# main.net
KiCad netlist of a schematic drawn in Altium Designer
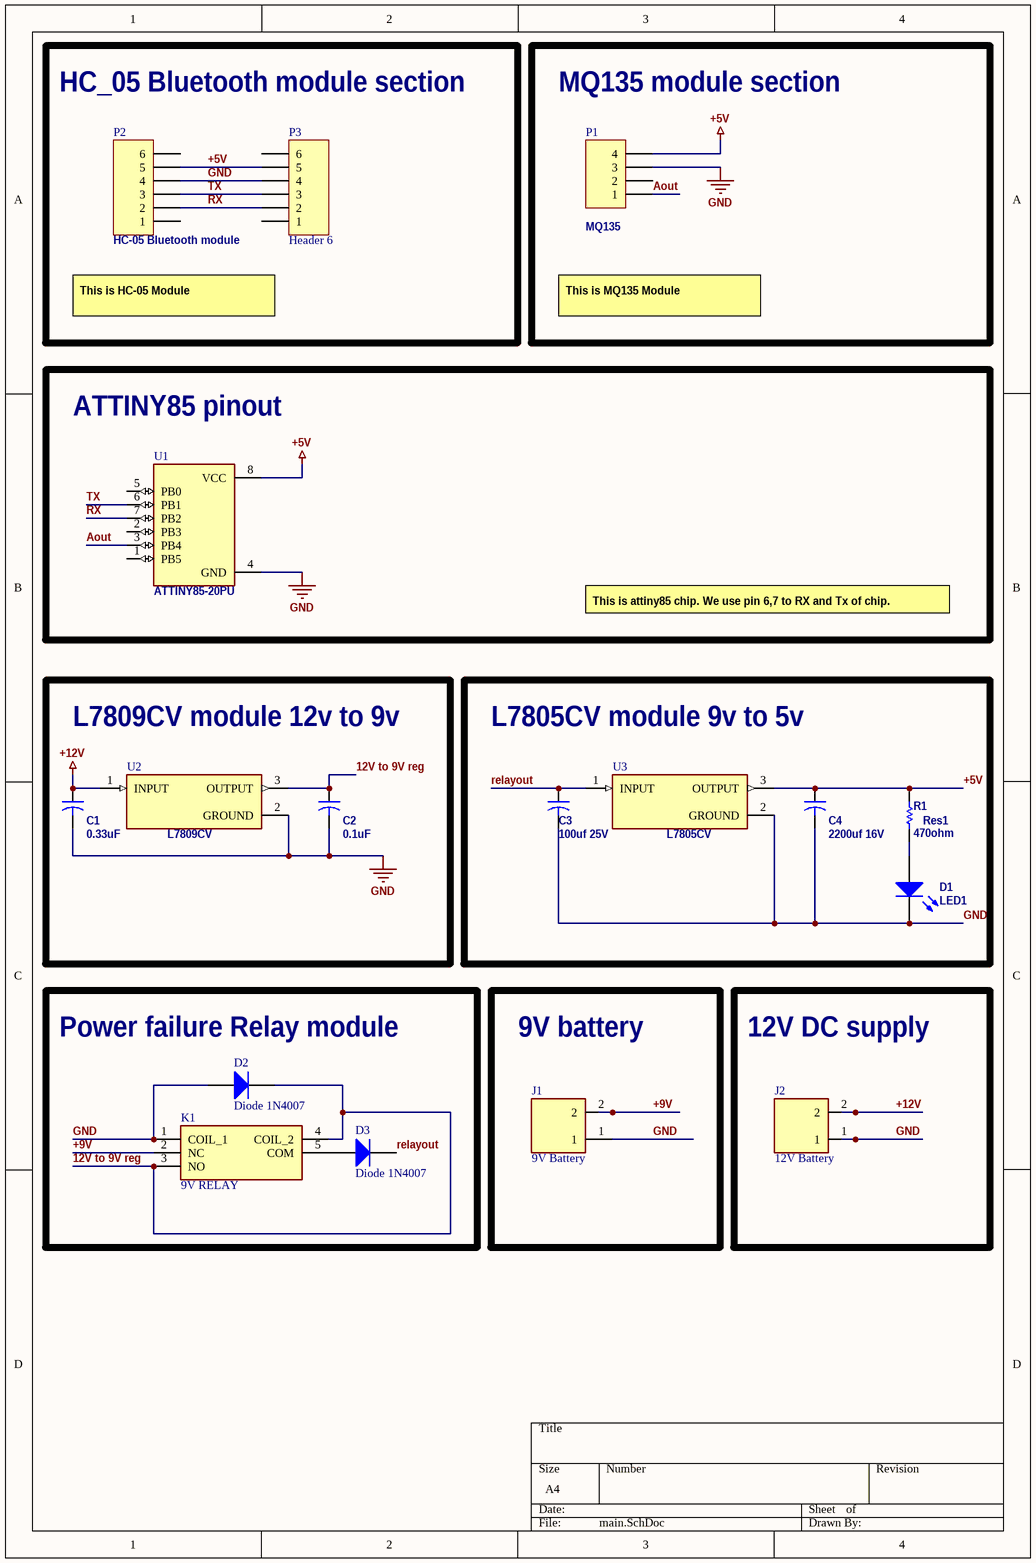
[diagram p0: main.SchDoc]

(export (version "E")
  (design (tool "Eeschema 10.0.6"))
  (components
    (comp (ref "C1")
      (value "0.33uF")
      (footprint "CAPR5-4X5")
      (description "Capacitor")
      (fields (field (name "PUBLISHER") "Altium Limited"))
      (libsource (lib "Miscellaneous Devices") (part "Cap2"))
    )
    (comp (ref "C2")
      (value "0.1uF")
      (footprint "CAPR5-4X5")
      (description "Capacitor")
      (fields (field (name "PUBLISHER") "Altium Limited"))
      (libsource (lib "Miscellaneous Devices") (part "Cap2"))
    )
    (comp (ref "C3")
      (value "100uf 25V")
      (footprint "CAPR5-4X5")
      (description "Capacitor")
      (fields (field (name "PUBLISHER") "Altium Limited"))
      (libsource (lib "Miscellaneous Devices") (part "Cap2"))
    )
    (comp (ref "C4")
      (value "2200uf 16V")
      (footprint "CAPR5-4X5")
      (description "Capacitor")
      (fields (field (name "PUBLISHER") "Altium Limited"))
      (libsource (lib "Miscellaneous Devices") (part "Cap2"))
    )
    (comp (ref "D1")
      (value "LED1")
      (footprint "LED-1")
      (description "Typical RED GaAs LED")
      (fields (field (name "PUBLISHER") "Altium Limited"))
      (libsource (lib "Miscellaneous Devices") (part "LED1"))
    )
    (comp (ref "D2")
      (value "Diode 1N4007")
      (footprint "DO-41")
      (description "1 Amp General Purpose Rectifier")
      (fields (field (name "PUBLISHER") "Altium Limited"))
      (libsource (lib "Miscellaneous Devices") (part "Diode 1N4007"))
    )
    (comp (ref "D3")
      (value "Diode 1N4007")
      (footprint "DO-41")
      (description "1 Amp General Purpose Rectifier")
      (fields (field (name "PUBLISHER") "Altium Limited"))
      (libsource (lib "Miscellaneous Devices") (part "Diode 1N4007"))
    )
    (comp (ref "J1")
      (value "9V Battery")
      (footprint "HANDSON_KF301-2P")
      (description "2 Pin Terminal Block 5mm Pitch")
      (fields (field (name "MP") "KF301-2P"))
      (libsource (lib "KF301-2P") (part "KF301-2P"))
    )
    (comp (ref "J2")
      (value "12V Battery")
      (footprint "HANDSON_KF301-2P")
      (description "2 Pin Terminal Block 5mm Pitch")
      (fields (field (name "MP") "KF301-2P"))
      (libsource (lib "KF301-2P") (part "KF301-2P"))
    )
    (comp (ref "K1")
      (value "9V RELAY")
      (footprint "JQC3FT731Z12VDC")
      (description "RELAY POWER 10A 12VDC 1C PCB TYPE (JS1) 5PIN QIANJ")
      (fields (field (name "MANUFACTURER_PART_NUMBER") "JQC-3F-(T73)-1Z-12VDC"))
      (libsource (lib "LIB_JQC-3F-_T73_-1Z-9VDC") (part "JQC-3F-_T73_-1Z-12VDC"))
    )
    (comp (ref "P1")
      (value "MQ135")
      (footprint "HDR1X4")
      (description "Header, 4-Pin")
      (fields (field (name "PUBLISHER") "Altium Limited"))
      (libsource (lib "Miscellaneous Connectors") (part "Header 4"))
    )
    (comp (ref "P2")
      (value "HC-05 Bluetooth module")
      (footprint "HDR1X6")
      (description "Header, 6-Pin")
      (fields (field (name "PUBLISHER") "Altium Limited"))
      (libsource (lib "Miscellaneous Connectors") (part "Header 6"))
    )
    (comp (ref "P3")
      (value "Header 6")
      (footprint "HDR1X6")
      (description "Header, 6-Pin")
      (fields (field (name "PUBLISHER") "Altium Limited"))
      (libsource (lib "") (part "Header 6_1"))
    )
    (comp (ref "R1")
      (value "Res1")
      (footprint "AXIAL-0.3")
      (description "Resistor")
      (fields (field (name "ALTIUM_VALUE") "470ohm") (field (name "PUBLISHER") "Altium Limited"))
      (libsource (lib "Miscellaneous Devices") (part "Res1"))
    )
    (comp (ref "U1")
      (value "ATTINY85-20PU")
      (footprint "DIP762W46P254L927H533Q8B")
      (fields (field (name "MF") "Microchip"))
      (libsource (lib "ATTINY85-20PU") (part "ATTINY85-20PU"))
    )
    (comp (ref "U2")
      (value "L7809CV")
      (footprint "TO255P1040X460X1968-3")
      (description "Linear Voltage Regulator IC Positive Fixed 1 Output 1.5A TO-220")
      (fields (field (name "MP") "L7805CV") (field (name "MF") "STMicroelectronics"))
      (libsource (lib "L7805CV") (part "L7805CV"))
    )
    (comp (ref "U3")
      (value "L7805CV")
      (footprint "TO255P1040X460X1968-3")
      (description "Linear Voltage Regulator IC Positive Fixed 1 Output 1.5A TO-220")
      (fields (field (name "MF") "STMicroelectronics"))
      (libsource (lib "L7805CV") (part "L7805CV"))
    )
  )
  (nets
    (net (code "1") (name "+5V") (class "Default")
      (node (ref "C4") (pin "1") (pinfunction "1_1") (pintype "passive"))
      (node (ref "P1") (pin "4") (pinfunction "4_4") (pintype "passive"))
      (node (ref "P2") (pin "5") (pinfunction "5_5") (pintype "passive"))
      (node (ref "P3") (pin "5") (pinfunction "5_5") (pintype "passive"))
      (node (ref "R1") (pin "2") (pinfunction "2_2") (pintype "passive"))
      (node (ref "U1") (pin "8") (pinfunction "VCC_8") (pintype "power_in"))
      (node (ref "U3") (pin "3") (pinfunction "OUTPUT_3") (pintype "output"))
    )
    (net (code "2") (name "+12V") (class "Default")
      (node (ref "C1") (pin "1") (pinfunction "1_1") (pintype "passive"))
      (node (ref "J2") (pin "2") (pinfunction "2_2") (pintype "passive"))
      (node (ref "U2") (pin "1") (pinfunction "INPUT_1") (pintype "input"))
    )
    (net (code "3") (name "/+9V") (class "Default")
      (node (ref "J1") (pin "2") (pinfunction "2_2") (pintype "passive"))
      (node (ref "K1") (pin "2") (pinfunction "NC_2") (pintype "passive"))
    )
    (net (code "4") (name "/12V to 9V reg") (class "Default")
      (node (ref "C2") (pin "1") (pinfunction "1_1") (pintype "passive"))
      (node (ref "D2") (pin "2") (pinfunction "K_2") (pintype "passive"))
      (node (ref "K1") (pin "3") (pinfunction "NO_3") (pintype "passive"))
      (node (ref "K1") (pin "4") (pinfunction "COIL_2_4") (pintype "passive"))
      (node (ref "U2") (pin "3") (pinfunction "OUTPUT_3") (pintype "output"))
    )
    (net (code "5") (name "/Aout") (class "Default")
      (node (ref "P1") (pin "1") (pinfunction "1_1") (pintype "passive"))
      (node (ref "U1") (pin "3") (pinfunction "PB4_3") (pintype "bidirectional"))
    )
    (net (code "6") (name "/RX") (class "Default")
      (node (ref "P2") (pin "2") (pinfunction "2_2") (pintype "passive"))
      (node (ref "P3") (pin "2") (pinfunction "2_2") (pintype "passive"))
      (node (ref "U1") (pin "7") (pinfunction "PB2_7") (pintype "bidirectional"))
    )
    (net (code "7") (name "/TX") (class "Default")
      (node (ref "P2") (pin "3") (pinfunction "3_3") (pintype "passive"))
      (node (ref "P3") (pin "3") (pinfunction "3_3") (pintype "passive"))
      (node (ref "U1") (pin "6") (pinfunction "PB1_6") (pintype "bidirectional"))
    )
    (net (code "8") (name "/relayout") (class "Default")
      (node (ref "C3") (pin "1") (pinfunction "1_1") (pintype "passive"))
      (node (ref "D3") (pin "2") (pinfunction "K_2") (pintype "passive"))
      (node (ref "U3") (pin "1") (pinfunction "INPUT_1") (pintype "input"))
    )
    (net (code "9") (name "GND") (class "Default")
      (node (ref "C1") (pin "2") (pinfunction "2_2") (pintype "passive"))
      (node (ref "C2") (pin "2") (pinfunction "2_2") (pintype "passive"))
      (node (ref "C3") (pin "2") (pinfunction "2_2") (pintype "passive"))
      (node (ref "C4") (pin "2") (pinfunction "2_2") (pintype "passive"))
      (node (ref "D1") (pin "2") (pinfunction "K_2") (pintype "passive"))
      (node (ref "D2") (pin "1") (pinfunction "A_1") (pintype "passive"))
      (node (ref "J1") (pin "1") (pinfunction "1_1") (pintype "passive"))
      (node (ref "J2") (pin "1") (pinfunction "1_1") (pintype "passive"))
      (node (ref "K1") (pin "1") (pinfunction "COIL_1_1") (pintype "passive"))
      (node (ref "P1") (pin "3") (pinfunction "3_3") (pintype "passive"))
      (node (ref "P2") (pin "4") (pinfunction "4_4") (pintype "passive"))
      (node (ref "P3") (pin "4") (pinfunction "4_4") (pintype "passive"))
      (node (ref "U1") (pin "4") (pinfunction "GND_4") (pintype "power_in"))
      (node (ref "U2") (pin "2") (pinfunction "GROUND_2") (pintype "power_in"))
      (node (ref "U3") (pin "2") (pinfunction "GROUND_2") (pintype "power_in"))
    )
    (net (code "10") (name "Net-(D1-A)") (class "Default")
      (node (ref "D1") (pin "1") (pinfunction "A_1") (pintype "passive"))
      (node (ref "R1") (pin "1") (pinfunction "1_1") (pintype "passive"))
    )
    (net (code "11") (name "Net-(D3-A)") (class "Default")
      (node (ref "D3") (pin "1") (pinfunction "A_1") (pintype "passive"))
      (node (ref "K1") (pin "5") (pinfunction "COM_5") (pintype "passive"))
    )
    (net (code "12") (name "unconnected-(P1-Pad2)") (class "Default")
      (node (ref "P1") (pin "2") (pinfunction "2_2") (pintype "passive"))
    )
    (net (code "13") (name "unconnected-(P2-Pad1)") (class "Default")
      (node (ref "P2") (pin "1") (pinfunction "1_1") (pintype "passive"))
    )
    (net (code "14") (name "unconnected-(P2-Pad6)") (class "Default")
      (node (ref "P2") (pin "6") (pinfunction "6_6") (pintype "passive"))
    )
    (net (code "15") (name "unconnected-(P3-Pad1)") (class "Default")
      (node (ref "P3") (pin "1") (pinfunction "1_1") (pintype "passive"))
    )
    (net (code "16") (name "unconnected-(P3-Pad6)") (class "Default")
      (node (ref "P3") (pin "6") (pinfunction "6_6") (pintype "passive"))
    )
    (net (code "17") (name "unconnected-(U1-PB0-Pad5)") (class "Default")
      (node (ref "U1") (pin "5") (pinfunction "PB0_5") (pintype "bidirectional"))
    )
    (net (code "18") (name "unconnected-(U1-PB3-Pad2)") (class "Default")
      (node (ref "U1") (pin "2") (pinfunction "PB3_2") (pintype "bidirectional"))
    )
    (net (code "19") (name "unconnected-(U1-PB5-Pad1)") (class "Default")
      (node (ref "U1") (pin "1") (pinfunction "PB5_1") (pintype "bidirectional"))
    )
  )
)
